# ext_abdoard.net
KiCad netlist of a schematic drawn in Altium Designer
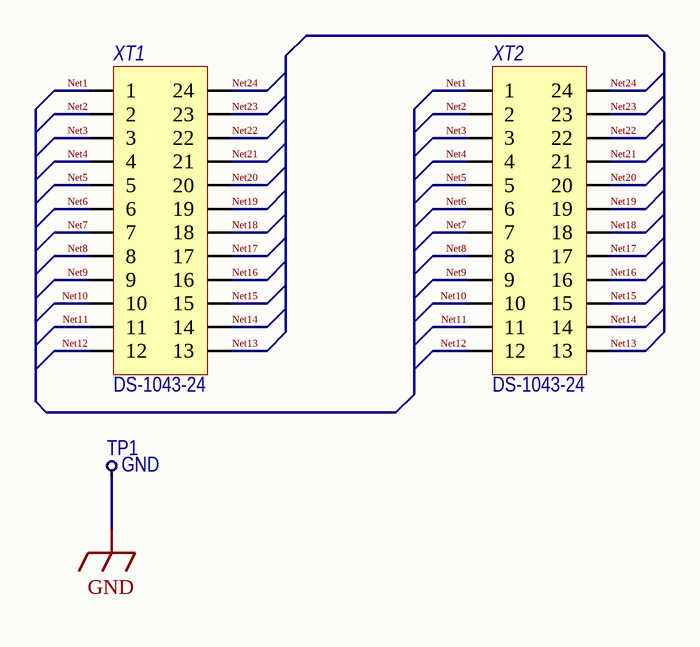
[diagram p0: ext_abdoard.SchDoc]

(export (version "E")
  (design (tool "Eeschema 10.0.6"))
  (components
    (comp (ref "TP1")
      (value "GND")
      (footprint "TestPoint:TestPoint")
      (fields (field (name "TP_NAME") "GND"))
      (libsource (lib "Connector") (part "TP"))
    )
    (comp (ref "XT1")
      (value "DS-1043-24")
      (footprint "bio_dnt_#1:DS-1043-24")
      (description "DIP-24 Zero Insertion Force (ZIF) socket")
      (fields (field (name "НАИМЕНОВАНИЕ") "DS-1043-24"))
      (libsource (lib "bio_dnt_#1") (part "DS-1043-24"))
    )
    (comp (ref "XT2")
      (value "DS-1043-24")
      (footprint "bio_dnt_#1:DS-1043-24")
      (description "DIP-24 Zero Insertion Force (ZIF) socket")
      (fields (field (name "НАИМЕНОВАНИЕ") "DS-1043-24"))
      (libsource (lib "bio_dnt_#1") (part "DS-1043-24"))
    )
  )
  (nets
    (net (code "1") (name "/Net1") (class "Default")
      (node (ref "XT1") (pin "1") (pinfunction "1_1") (pintype "passive"))
      (node (ref "XT2") (pin "1") (pinfunction "1_1") (pintype "passive"))
    )
    (net (code "2") (name "/Net2") (class "Default")
      (node (ref "XT1") (pin "2") (pinfunction "2_2") (pintype "passive"))
      (node (ref "XT2") (pin "2") (pinfunction "2_2") (pintype "passive"))
    )
    (net (code "3") (name "/Net3") (class "Default")
      (node (ref "XT1") (pin "3") (pinfunction "3_3") (pintype "passive"))
      (node (ref "XT2") (pin "3") (pinfunction "3_3") (pintype "passive"))
    )
    (net (code "4") (name "/Net4") (class "Default")
      (node (ref "XT1") (pin "4") (pinfunction "4_4") (pintype "passive"))
      (node (ref "XT2") (pin "4") (pinfunction "4_4") (pintype "passive"))
    )
    (net (code "5") (name "/Net5") (class "Default")
      (node (ref "XT1") (pin "5") (pinfunction "5_5") (pintype "passive"))
      (node (ref "XT2") (pin "5") (pinfunction "5_5") (pintype "passive"))
    )
    (net (code "6") (name "/Net6") (class "Default")
      (node (ref "XT1") (pin "6") (pinfunction "6_6") (pintype "passive"))
      (node (ref "XT2") (pin "6") (pinfunction "6_6") (pintype "passive"))
    )
    (net (code "7") (name "/Net7") (class "Default")
      (node (ref "XT1") (pin "7") (pinfunction "7_7") (pintype "passive"))
      (node (ref "XT2") (pin "7") (pinfunction "7_7") (pintype "passive"))
    )
    (net (code "8") (name "/Net8") (class "Default")
      (node (ref "XT1") (pin "8") (pinfunction "8_8") (pintype "passive"))
      (node (ref "XT2") (pin "8") (pinfunction "8_8") (pintype "passive"))
    )
    (net (code "9") (name "/Net9") (class "Default")
      (node (ref "XT1") (pin "9") (pinfunction "9_9") (pintype "passive"))
      (node (ref "XT2") (pin "9") (pinfunction "9_9") (pintype "passive"))
    )
    (net (code "10") (name "/Net10") (class "Default")
      (node (ref "XT1") (pin "10") (pinfunction "10_10") (pintype "passive"))
      (node (ref "XT2") (pin "10") (pinfunction "10_10") (pintype "passive"))
    )
    (net (code "11") (name "/Net11") (class "Default")
      (node (ref "XT1") (pin "11") (pinfunction "11_11") (pintype "passive"))
      (node (ref "XT2") (pin "11") (pinfunction "11_11") (pintype "passive"))
    )
    (net (code "12") (name "/Net12") (class "Default")
      (node (ref "XT1") (pin "12") (pinfunction "12_12") (pintype "passive"))
      (node (ref "XT2") (pin "12") (pinfunction "12_12") (pintype "passive"))
    )
    (net (code "13") (name "/Net13") (class "Default")
      (node (ref "XT1") (pin "13") (pinfunction "13_13") (pintype "passive"))
      (node (ref "XT2") (pin "13") (pinfunction "13_13") (pintype "passive"))
    )
    (net (code "14") (name "/Net14") (class "Default")
      (node (ref "XT1") (pin "14") (pinfunction "14_14") (pintype "passive"))
      (node (ref "XT2") (pin "14") (pinfunction "14_14") (pintype "passive"))
    )
    (net (code "15") (name "/Net15") (class "Default")
      (node (ref "XT1") (pin "15") (pinfunction "15_15") (pintype "passive"))
      (node (ref "XT2") (pin "15") (pinfunction "15_15") (pintype "passive"))
    )
    (net (code "16") (name "/Net16") (class "Default")
      (node (ref "XT1") (pin "16") (pinfunction "16_16") (pintype "passive"))
      (node (ref "XT2") (pin "16") (pinfunction "16_16") (pintype "passive"))
    )
    (net (code "17") (name "/Net17") (class "Default")
      (node (ref "XT1") (pin "17") (pinfunction "17_17") (pintype "passive"))
      (node (ref "XT2") (pin "17") (pinfunction "17_17") (pintype "passive"))
    )
    (net (code "18") (name "/Net18") (class "Default")
      (node (ref "XT1") (pin "18") (pinfunction "18_18") (pintype "passive"))
      (node (ref "XT2") (pin "18") (pinfunction "18_18") (pintype "passive"))
    )
    (net (code "19") (name "/Net19") (class "Default")
      (node (ref "XT1") (pin "19") (pinfunction "19_19") (pintype "passive"))
      (node (ref "XT2") (pin "19") (pinfunction "19_19") (pintype "passive"))
    )
    (net (code "20") (name "/Net20") (class "Default")
      (node (ref "XT1") (pin "20") (pinfunction "20_20") (pintype "passive"))
      (node (ref "XT2") (pin "20") (pinfunction "20_20") (pintype "passive"))
    )
    (net (code "21") (name "/Net21") (class "Default")
      (node (ref "XT1") (pin "21") (pinfunction "21_21") (pintype "passive"))
      (node (ref "XT2") (pin "21") (pinfunction "21_21") (pintype "passive"))
    )
    (net (code "22") (name "/Net22") (class "Default")
      (node (ref "XT1") (pin "22") (pinfunction "22_22") (pintype "passive"))
      (node (ref "XT2") (pin "22") (pinfunction "22_22") (pintype "passive"))
    )
    (net (code "23") (name "/Net23") (class "Default")
      (node (ref "XT1") (pin "23") (pinfunction "23_23") (pintype "passive"))
      (node (ref "XT2") (pin "23") (pinfunction "23_23") (pintype "passive"))
    )
    (net (code "24") (name "/Net24") (class "Default")
      (node (ref "XT1") (pin "24") (pinfunction "24_24") (pintype "passive"))
      (node (ref "XT2") (pin "24") (pinfunction "24_24") (pintype "passive"))
    )
    (net (code "25") (name "GND") (class "Default")
      (node (ref "TP1") (pin "0") (pinfunction "TP_0") (pintype "passive"))
    )
  )
)
